# CPUPower.net
KiCad netlist of a schematic drawn in Altium Designer
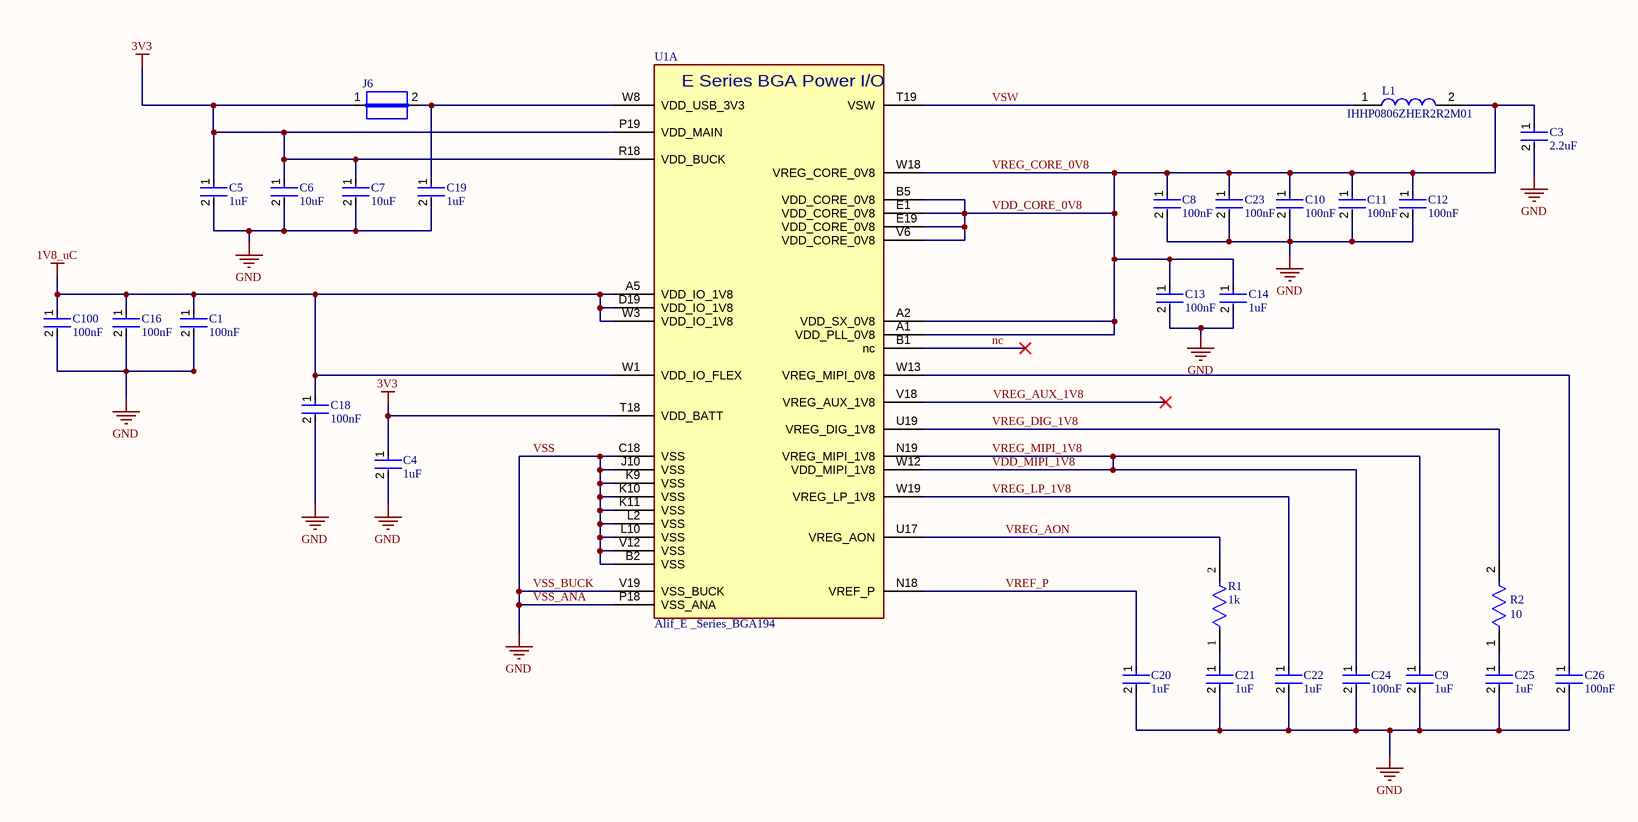
[diagram p0: CPUPower.SchDoc]

(export (version "E")
  (design (tool "Eeschema 10.0.6"))
  (components
    (comp (ref "C1")
      (value "100nF")
      (footprint "FP-C0603X104K3RACTU-MFG")
      (description "CAP CER 0.1UF 25V X7R 0603")
      (fields (field (name "VOLTAGE") "25V") (field (name "TOLERANCE") "10%"))
      (libsource (lib "Altium Content Vault") (part "02cd4be3c70576c341d710602a673aa"))
    )
    (comp (ref "C3")
      (value "2.2uF")
      (footprint "FP-CC0603-DA-MFG")
      (description "CAP CER 2.2UF 6.3V X5R 0603")
      (fields (field (name "TOLERANCE") "0.1") (field (name "MANUFACTURER") "YAGEO"))
      (libsource (lib "Altium Content Vault") (part "11868f565c42a9108669ba33697ecf6"))
    )
    (comp (ref "C4")
      (value "1uF")
      (footprint "FP-CL10-IPC_C")
      (libsource (lib "Gustav Eckerbom") (part "b4654b650e69147ec39a6b967a45e02"))
    )
    (comp (ref "C5")
      (value "1uF")
      (footprint "FP-CL10-IPC_C")
      (libsource (lib "Gustav Eckerbom") (part "b4654b650e69147ec39a6b967a45e02"))
    )
    (comp (ref "C6")
      (value "10uF")
      (footprint "FP-CC0603-0_15-0_95-IPC_C")
      (libsource (lib "Gustav Eckerbom") (part "02cd4be3c70576c341d710602a673aa"))
    )
    (comp (ref "C7")
      (value "10uF")
      (footprint "FP-CC0603-0_15-0_95-IPC_C")
      (libsource (lib "Gustav Eckerbom") (part "02cd4be3c70576c341d710602a673aa"))
    )
    (comp (ref "C8")
      (value "100nF")
      (footprint "FP-C0603X104K3RACTU-MFG")
      (description "CAP CER 0.1UF 25V X7R 0603")
      (fields (field (name "VOLTAGE") "25V") (field (name "TOLERANCE") "10%"))
      (libsource (lib "Altium Content Vault") (part "02cd4be3c70576c341d710602a673aa"))
    )
    (comp (ref "C9")
      (value "1uF")
      (footprint "FP-CL10-IPC_C")
      (libsource (lib "Gustav Eckerbom") (part "b4654b650e69147ec39a6b967a45e02"))
    )
    (comp (ref "C10")
      (value "100nF")
      (footprint "FP-C0603X104K3RACTU-MFG")
      (description "CAP CER 0.1UF 25V X7R 0603")
      (fields (field (name "VOLTAGE") "25V") (field (name "TOLERANCE") "10%"))
      (libsource (lib "Altium Content Vault") (part "02cd4be3c70576c341d710602a673aa"))
    )
    (comp (ref "C11")
      (value "100nF")
      (footprint "FP-C0603X104K3RACTU-MFG")
      (description "CAP CER 0.1UF 25V X7R 0603")
      (fields (field (name "VOLTAGE") "25V") (field (name "TOLERANCE") "10%"))
      (libsource (lib "Altium Content Vault") (part "02cd4be3c70576c341d710602a673aa"))
    )
    (comp (ref "C12")
      (value "100nF")
      (footprint "FP-C0603X104K3RACTU-MFG")
      (description "CAP CER 0.1UF 25V X7R 0603")
      (fields (field (name "VOLTAGE") "25V") (field (name "TOLERANCE") "10%"))
      (libsource (lib "Altium Content Vault") (part "02cd4be3c70576c341d710602a673aa"))
    )
    (comp (ref "C13")
      (value "100nF")
      (footprint "FP-C0603X104K3RACTU-MFG")
      (description "CAP CER 0.1UF 25V X7R 0603")
      (fields (field (name "VOLTAGE") "25V") (field (name "TOLERANCE") "10%"))
      (libsource (lib "Altium Content Vault") (part "02cd4be3c70576c341d710602a673aa"))
    )
    (comp (ref "C14")
      (value "1uF")
      (footprint "FP-CL10-IPC_C")
      (libsource (lib "Gustav Eckerbom") (part "b4654b650e69147ec39a6b967a45e02"))
    )
    (comp (ref "C16")
      (value "100nF")
      (footprint "FP-C0603X104K3RACTU-MFG")
      (description "CAP CER 0.1UF 25V X7R 0603")
      (fields (field (name "VOLTAGE") "25V") (field (name "TOLERANCE") "10%"))
      (libsource (lib "Altium Content Vault") (part "02cd4be3c70576c341d710602a673aa"))
    )
    (comp (ref "C18")
      (value "100nF")
      (footprint "FP-C0603X104K3RACTU-MFG")
      (description "CAP CER 0.1UF 25V X7R 0603")
      (fields (field (name "VOLTAGE") "25V") (field (name "TOLERANCE") "10%"))
      (libsource (lib "Altium Content Vault") (part "02cd4be3c70576c341d710602a673aa"))
    )
    (comp (ref "C19")
      (value "1uF")
      (footprint "FP-CL10-IPC_C")
      (libsource (lib "Gustav Eckerbom") (part "b4654b650e69147ec39a6b967a45e02"))
    )
    (comp (ref "C20")
      (value "1uF")
      (footprint "FP-CL10-IPC_C")
      (libsource (lib "Gustav Eckerbom") (part "b4654b650e69147ec39a6b967a45e02"))
    )
    (comp (ref "C21")
      (value "1uF")
      (footprint "FP-CL10-IPC_C")
      (libsource (lib "Gustav Eckerbom") (part "b4654b650e69147ec39a6b967a45e02"))
    )
    (comp (ref "C22")
      (value "1uF")
      (footprint "FP-CL10-IPC_C")
      (libsource (lib "Gustav Eckerbom") (part "b4654b650e69147ec39a6b967a45e02"))
    )
    (comp (ref "C23")
      (value "100nF")
      (footprint "FP-C0603X104K3RACTU-MFG")
      (description "CAP CER 0.1UF 25V X7R 0603")
      (fields (field (name "VOLTAGE") "25V") (field (name "TOLERANCE") "10%"))
      (libsource (lib "Altium Content Vault") (part "02cd4be3c70576c341d710602a673aa"))
    )
    (comp (ref "C24")
      (value "100nF")
      (footprint "FP-C0603X104K3RACTU-MFG")
      (description "CAP CER 0.1UF 25V X7R 0603")
      (fields (field (name "VOLTAGE") "25V") (field (name "TOLERANCE") "10%"))
      (libsource (lib "Altium Content Vault") (part "02cd4be3c70576c341d710602a673aa"))
    )
    (comp (ref "C25")
      (value "1uF")
      (footprint "FP-CL10-IPC_C")
      (libsource (lib "Gustav Eckerbom") (part "b4654b650e69147ec39a6b967a45e02"))
    )
    (comp (ref "C26")
      (value "100nF")
      (footprint "FP-C0603X104K3RACTU-MFG")
      (description "CAP CER 0.1UF 25V X7R 0603")
      (fields (field (name "VOLTAGE") "25V") (field (name "TOLERANCE") "10%"))
      (libsource (lib "Altium Content Vault") (part "02cd4be3c70576c341d710602a673aa"))
    )
    (comp (ref "C100")
      (value "100nF")
      (footprint "FP-C0603X104K3RACTU-MFG")
      (description "CAP CER 0.1UF 25V X7R 0603")
      (fields (field (name "VOLTAGE") "25V") (field (name "TOLERANCE") "10%"))
      (libsource (lib "Altium Content Vault") (part "02cd4be3c70576c341d710602a673aa"))
    )
    (comp (ref "J6")
      (value "JUMPER")
      (footprint "JUMPER")
      (libsource (lib "Gustav Eckerbom") (part "JUMPER"))
    )
    (comp (ref "L1")
      (value "IHHP0806ZHER2R2M01")
      (footprint "SamacSys:INDC2016X80N")
      (description "Inductor")
      (fields (field (name "MOUSER PART NUMBER") "70-IHHP0806ZHR2R2M01"))
      (libsource (lib "*") (part "IHHP0806ZHER2R2M01"))
    )
    (comp (ref "R1")
      (value "1k")
      (footprint "FP-RCA0603-e3-MFG")
      (fields (field (name "TOLERANCE") "1%"))
      (libsource (lib "Altium Content Vault") (part "1029c3af85768c4190bb7ad29bc67b5"))
    )
    (comp (ref "R2")
      (value "10")
      (footprint "FP-RT0603-MFG")
      (description "RES SMD 10 OHM 1% 1/10W 0603")
      (fields
        (field (name "MANUFACTURER PART NUMBER") "RT0603FRE0710RL")
        (field (name "MANUFACTURER") "Yageo")
      )
      (libsource (lib "Altium Content Vault") (part "1029c3af85768c4190bb7ad29bc67b5"))
    )
    (comp (ref "U1")
      (value "Alif_E _Series_BGA194")
      (footprint "BGA194 _CENTERED")
      (description "IC,Alif E7 MCU, Rev B silicon,BGA194")
      (libsource (lib "AlifSoC") (part "E7_B0_194BGA"))
    )
  )
  (nets
    (net (code "1") (name "/VDD_CORE_0V8") (class "Default")
      (node (ref "C10") (pin "1") (pinfunction "1_1") (pintype "passive"))
      (node (ref "C11") (pin "1") (pinfunction "1_1") (pintype "passive"))
      (node (ref "C12") (pin "1") (pinfunction "1_1") (pintype "passive"))
      (node (ref "C13") (pin "1") (pinfunction "1_1") (pintype "passive"))
      (node (ref "C14") (pin "1") (pinfunction "1_1") (pintype "passive"))
      (node (ref "C23") (pin "1") (pinfunction "1_1") (pintype "passive"))
      (node (ref "C3") (pin "1") (pinfunction "1_1") (pintype "passive"))
      (node (ref "C8") (pin "1") (pinfunction "1_1") (pintype "passive"))
      (node (ref "L1") (pin "2") (pinfunction "2_2") (pintype "passive"))
      (node (ref "U1") (pin "A1") (pinfunction "VDD_PLL_0V8_A1") (pintype "power_in"))
      (node (ref "U1") (pin "A2") (pinfunction "VDD_SX_0V8_A2") (pintype "power_in"))
      (node (ref "U1") (pin "B5") (pinfunction "VDD_CORE_0V8_B5") (pintype "power_in"))
      (node (ref "U1") (pin "E1") (pinfunction "VDD_CORE_0V8_E1") (pintype "power_in"))
      (node (ref "U1") (pin "E19") (pinfunction "VDD_CORE_0V8_E19") (pintype "power_in"))
      (node (ref "U1") (pin "V6") (pinfunction "VDD_CORE_0V8_V6") (pintype "power_in"))
      (node (ref "U1") (pin "W18") (pinfunction "VREG_CORE_0V8_W18") (pintype "power_in"))
    )
    (net (code "2") (name "/VDD_MIPI_1V8") (class "Default")
      (node (ref "C24") (pin "1") (pinfunction "1_1") (pintype "passive"))
      (node (ref "C9") (pin "1") (pinfunction "1_1") (pintype "passive"))
      (node (ref "U1") (pin "N19") (pinfunction "VREG_MIPI_1V8_N19") (pintype "power_in"))
      (node (ref "U1") (pin "W12") (pinfunction "VDD_MIPI_1V8_W12") (pintype "power_in"))
    )
    (net (code "3") (name "/VREF_P") (class "Default")
      (node (ref "C20") (pin "1") (pinfunction "1_1") (pintype "passive"))
      (node (ref "U1") (pin "N18") (pinfunction "VREF_P_N18") (pintype "passive"))
    )
    (net (code "4") (name "/VREG_AON") (class "Default")
      (node (ref "R1") (pin "2") (pinfunction "2_2") (pintype "passive"))
      (node (ref "U1") (pin "U17") (pinfunction "VREG_AON_U17") (pintype "power_in"))
    )
    (net (code "5") (name "/VREG_AUX_1V8") (class "Default")
      (node (ref "U1") (pin "V18") (pinfunction "VREG_AUX_1V8_V18") (pintype "power_in+no_connect"))
    )
    (net (code "6") (name "/VREG_DIG_1V8") (class "Default")
      (node (ref "R2") (pin "2") (pinfunction "2_2") (pintype "passive"))
      (node (ref "U1") (pin "U19") (pinfunction "VREG_DIG_1V8_U19") (pintype "power_in"))
    )
    (net (code "7") (name "/VREG_LP_1V8") (class "Default")
      (node (ref "C22") (pin "1") (pinfunction "1_1") (pintype "passive"))
      (node (ref "U1") (pin "W19") (pinfunction "VREG_LP_1V8_W19") (pintype "power_in"))
    )
    (net (code "8") (name "/VSW") (class "Default")
      (node (ref "L1") (pin "1") (pinfunction "1_1") (pintype "passive"))
      (node (ref "U1") (pin "T19") (pinfunction "VSW_T19") (pintype "passive"))
    )
    (net (code "9") (name "/nc") (class "Default")
      (node (ref "U1") (pin "B1") (pinfunction "nc_B1") (pintype "power_in+no_connect"))
    )
    (net (code "10") (name "1V8_uC") (class "Default")
      (node (ref "C1") (pin "1") (pinfunction "1_1") (pintype "passive"))
      (node (ref "C100") (pin "1") (pinfunction "1_1") (pintype "passive"))
      (node (ref "C16") (pin "1") (pinfunction "1_1") (pintype "passive"))
      (node (ref "C18") (pin "1") (pinfunction "1_1") (pintype "passive"))
      (node (ref "U1") (pin "A5") (pinfunction "VDD_IO_1V8_A5") (pintype "power_in"))
      (node (ref "U1") (pin "D19") (pinfunction "VDD_IO_1V8_D19") (pintype "power_in"))
      (node (ref "U1") (pin "W1") (pinfunction "VDD_IO_FLEX_W1") (pintype "power_in"))
      (node (ref "U1") (pin "W3") (pinfunction "VDD_IO_1V8_W3") (pintype "power_in"))
    )
    (net (code "11") (name "3V3") (class "Default")
      (node (ref "C4") (pin "1") (pinfunction "1_1") (pintype "passive"))
      (node (ref "C5") (pin "1") (pinfunction "1_1") (pintype "passive"))
      (node (ref "C6") (pin "1") (pinfunction "1_1") (pintype "passive"))
      (node (ref "C7") (pin "1") (pinfunction "1_1") (pintype "passive"))
      (node (ref "J6") (pin "1") (pinfunction "1_1") (pintype "passive"))
      (node (ref "U1") (pin "P19") (pinfunction "VDD_MAIN_P19") (pintype "power_in"))
      (node (ref "U1") (pin "R18") (pinfunction "VDD_BUCK_R18") (pintype "power_in"))
      (node (ref "U1") (pin "T18") (pinfunction "VDD_BATT_T18") (pintype "power_in"))
    )
    (net (code "12") (name "GND") (class "Default")
      (node (ref "C1") (pin "2") (pinfunction "2_2") (pintype "passive"))
      (node (ref "C10") (pin "2") (pinfunction "2_2") (pintype "passive"))
      (node (ref "C100") (pin "2") (pinfunction "2_2") (pintype "passive"))
      (node (ref "C11") (pin "2") (pinfunction "2_2") (pintype "passive"))
      (node (ref "C12") (pin "2") (pinfunction "2_2") (pintype "passive"))
      (node (ref "C13") (pin "2") (pinfunction "2_2") (pintype "passive"))
      (node (ref "C14") (pin "2") (pinfunction "2_2") (pintype "passive"))
      (node (ref "C16") (pin "2") (pinfunction "2_2") (pintype "passive"))
      (node (ref "C18") (pin "2") (pinfunction "2_2") (pintype "passive"))
      (node (ref "C19") (pin "2") (pinfunction "2_2") (pintype "passive"))
      (node (ref "C20") (pin "2") (pinfunction "2_2") (pintype "passive"))
      (node (ref "C21") (pin "2") (pinfunction "2_2") (pintype "passive"))
      (node (ref "C22") (pin "2") (pinfunction "2_2") (pintype "passive"))
      (node (ref "C23") (pin "2") (pinfunction "2_2") (pintype "passive"))
      (node (ref "C24") (pin "2") (pinfunction "2_2") (pintype "passive"))
      (node (ref "C25") (pin "2") (pinfunction "2_2") (pintype "passive"))
      (node (ref "C26") (pin "2") (pinfunction "2_2") (pintype "passive"))
      (node (ref "C3") (pin "2") (pinfunction "2_2") (pintype "passive"))
      (node (ref "C4") (pin "2") (pinfunction "2_2") (pintype "passive"))
      (node (ref "C5") (pin "2") (pinfunction "2_2") (pintype "passive"))
      (node (ref "C6") (pin "2") (pinfunction "2_2") (pintype "passive"))
      (node (ref "C7") (pin "2") (pinfunction "2_2") (pintype "passive"))
      (node (ref "C8") (pin "2") (pinfunction "2_2") (pintype "passive"))
      (node (ref "C9") (pin "2") (pinfunction "2_2") (pintype "passive"))
      (node (ref "U1") (pin "B2") (pinfunction "VSS_B2") (pintype "power_in"))
      (node (ref "U1") (pin "C18") (pinfunction "VSS_C18") (pintype "power_in"))
      (node (ref "U1") (pin "J10") (pinfunction "VSS_J10") (pintype "power_in"))
      (node (ref "U1") (pin "K10") (pinfunction "VSS_K10") (pintype "power_in"))
      (node (ref "U1") (pin "K11") (pinfunction "VSS_K11") (pintype "power_in"))
      (node (ref "U1") (pin "K9") (pinfunction "VSS_K9") (pintype "power_in"))
      (node (ref "U1") (pin "L10") (pinfunction "VSS_L10") (pintype "power_in"))
      (node (ref "U1") (pin "L2") (pinfunction "VSS_L2") (pintype "power_in"))
      (node (ref "U1") (pin "P18") (pinfunction "VSS_ANA_P18") (pintype "power_in"))
      (node (ref "U1") (pin "V12") (pinfunction "VSS_V12") (pintype "power_in"))
      (node (ref "U1") (pin "V19") (pinfunction "VSS_BUCK_V19") (pintype "power_in"))
    )
    (net (code "13") (name "Net-(C21-Pad1)") (class "Default")
      (node (ref "C21") (pin "1") (pinfunction "1_1") (pintype "passive"))
      (node (ref "R1") (pin "1") (pinfunction "1_1") (pintype "passive"))
    )
    (net (code "14") (name "Net-(C25-Pad1)") (class "Default")
      (node (ref "C25") (pin "1") (pinfunction "1_1") (pintype "passive"))
      (node (ref "R2") (pin "1") (pinfunction "1_1") (pintype "passive"))
    )
    (net (code "15") (name "Net-(U1A-VDD_USB_3V3)") (class "Default")
      (node (ref "C19") (pin "1") (pinfunction "1_1") (pintype "passive"))
      (node (ref "J6") (pin "2") (pinfunction "2_2") (pintype "passive"))
      (node (ref "U1") (pin "W8") (pinfunction "VDD_USB_3V3_W8") (pintype "power_in"))
    )
    (net (code "16") (name "Net-(U1A-VREG_MIPI_0V8)") (class "Default")
      (node (ref "C26") (pin "1") (pinfunction "1_1") (pintype "passive"))
      (node (ref "U1") (pin "W13") (pinfunction "VREG_MIPI_0V8_W13") (pintype "power_in"))
    )
  )
)
